# RJ45.net
KiCad netlist of a schematic drawn in Altium Designer
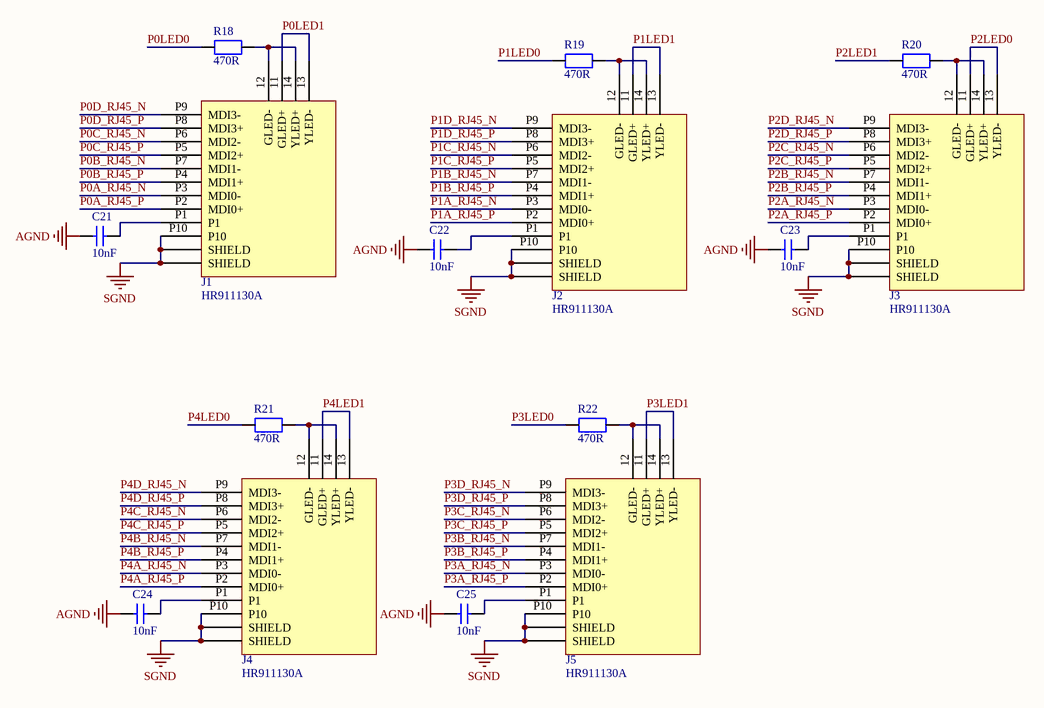
[diagram p0: RJ45.SchDoc]

(export (version "E")
  (design (tool "Eeschema 10.0.6"))
  (components
    (comp (ref "C21")
      (value "10nF")
      (footprint "C-0603")
      (description "C-0603")
      (libsource (lib "Switch_Schlib") (part "C-0603"))
    )
    (comp (ref "C22")
      (value "10nF")
      (footprint "C-0603")
      (description "C-0603")
      (libsource (lib "Switch_Schlib") (part "C-0603"))
    )
    (comp (ref "C23")
      (value "10nF")
      (footprint "C-0603")
      (description "C-0603")
      (libsource (lib "Switch_Schlib") (part "C-0603"))
    )
    (comp (ref "C24")
      (value "10nF")
      (footprint "C-0603")
      (description "C-0603")
      (libsource (lib "Switch_Schlib") (part "C-0603"))
    )
    (comp (ref "C25")
      (value "10nF")
      (footprint "C-0603")
      (description "C-0603")
      (libsource (lib "Switch_Schlib") (part "C-0603"))
    )
    (comp (ref "J1")
      (value "HR911130A")
      (footprint "RJ45")
      (libsource (lib "Switch_Schlib") (part "HR911130A"))
    )
    (comp (ref "J2")
      (value "HR911130A")
      (footprint "RJ45")
      (libsource (lib "Switch_Schlib") (part "HR911130A"))
    )
    (comp (ref "J3")
      (value "HR911130A")
      (footprint "RJ45")
      (libsource (lib "Switch_Schlib") (part "HR911130A"))
    )
    (comp (ref "J4")
      (value "HR911130A")
      (footprint "RJ45")
      (libsource (lib "Switch_Schlib") (part "HR911130A"))
    )
    (comp (ref "J5")
      (value "HR911130A")
      (footprint "RJ45")
      (libsource (lib "Switch_Schlib") (part "HR911130A"))
    )
    (comp (ref "R18")
      (value "470R")
      (footprint "RESMELF3515L")
      (description "CSR-0204")
      (libsource (lib "Switch_Schlib") (part "CSR-0204"))
    )
    (comp (ref "R19")
      (value "470R")
      (footprint "RESMELF3515L")
      (description "CSR-0204")
      (libsource (lib "Switch_Schlib") (part "CSR-0204"))
    )
    (comp (ref "R20")
      (value "470R")
      (footprint "RESMELF3515L")
      (description "CSR-0204")
      (libsource (lib "Switch_Schlib") (part "CSR-0204"))
    )
    (comp (ref "R21")
      (value "470R")
      (footprint "RESMELF3515L")
      (description "CSR-0204")
      (libsource (lib "Switch_Schlib") (part "CSR-0204"))
    )
    (comp (ref "R22")
      (value "470R")
      (footprint "RESMELF3515L")
      (description "CSR-0204")
      (libsource (lib "Switch_Schlib") (part "CSR-0204"))
    )
  )
  (nets
    (net (code "1") (name "/P0A_RJ45_N") (class "Default")
      (node (ref "J1") (pin "P3") (pinfunction "MDI0-_P3") (pintype "passive"))
    )
    (net (code "2") (name "/P0A_RJ45_P") (class "Default")
      (node (ref "J1") (pin "P2") (pinfunction "MDI0+_P2") (pintype "passive"))
    )
    (net (code "3") (name "/P0B_RJ45_N") (class "Default")
      (node (ref "J1") (pin "P7") (pinfunction "MDI1-_P7") (pintype "passive"))
    )
    (net (code "4") (name "/P0B_RJ45_P") (class "Default")
      (node (ref "J1") (pin "P4") (pinfunction "MDI1+_P4") (pintype "passive"))
    )
    (net (code "5") (name "/P0C_RJ45_N") (class "Default")
      (node (ref "J1") (pin "P6") (pinfunction "MDI2-_P6") (pintype "passive"))
    )
    (net (code "6") (name "/P0C_RJ45_P") (class "Default")
      (node (ref "J1") (pin "P5") (pinfunction "MDI2+_P5") (pintype "passive"))
    )
    (net (code "7") (name "/P0D_RJ45_N") (class "Default")
      (node (ref "J1") (pin "P9") (pinfunction "MDI3-_P9") (pintype "passive"))
    )
    (net (code "8") (name "/P0D_RJ45_P") (class "Default")
      (node (ref "J1") (pin "P8") (pinfunction "MDI3+_P8") (pintype "passive"))
    )
    (net (code "9") (name "/P0LED0") (class "Default") (node (ref "R18") (pin "1") (pintype "passive")))
    (net (code "10") (name "/P0LED1") (class "Default")
      (node (ref "J1") (pin "11") (pinfunction "GLED+_11") (pintype "passive"))
      (node (ref "J1") (pin "13") (pinfunction "YLED-_13") (pintype "passive"))
    )
    (net (code "11") (name "/P1A_RJ45_N") (class "Default")
      (node (ref "J2") (pin "P3") (pinfunction "MDI0-_P3") (pintype "passive"))
    )
    (net (code "12") (name "/P1A_RJ45_P") (class "Default")
      (node (ref "J2") (pin "P2") (pinfunction "MDI0+_P2") (pintype "passive"))
    )
    (net (code "13") (name "/P1B_RJ45_N") (class "Default")
      (node (ref "J2") (pin "P7") (pinfunction "MDI1-_P7") (pintype "passive"))
    )
    (net (code "14") (name "/P1B_RJ45_P") (class "Default")
      (node (ref "J2") (pin "P4") (pinfunction "MDI1+_P4") (pintype "passive"))
    )
    (net (code "15") (name "/P1C_RJ45_N") (class "Default")
      (node (ref "J2") (pin "P6") (pinfunction "MDI2-_P6") (pintype "passive"))
    )
    (net (code "16") (name "/P1C_RJ45_P") (class "Default")
      (node (ref "J2") (pin "P5") (pinfunction "MDI2+_P5") (pintype "passive"))
    )
    (net (code "17") (name "/P1D_RJ45_N") (class "Default")
      (node (ref "J2") (pin "P9") (pinfunction "MDI3-_P9") (pintype "passive"))
    )
    (net (code "18") (name "/P1D_RJ45_P") (class "Default")
      (node (ref "J2") (pin "P8") (pinfunction "MDI3+_P8") (pintype "passive"))
    )
    (net (code "19") (name "/P1LED0") (class "Default") (node (ref "R19") (pin "1") (pintype "passive")))
    (net (code "20") (name "/P1LED1") (class "Default")
      (node (ref "J2") (pin "11") (pinfunction "GLED+_11") (pintype "passive"))
      (node (ref "J2") (pin "13") (pinfunction "YLED-_13") (pintype "passive"))
    )
    (net (code "21") (name "/P2A_RJ45_N") (class "Default")
      (node (ref "J3") (pin "P3") (pinfunction "MDI0-_P3") (pintype "passive"))
    )
    (net (code "22") (name "/P2A_RJ45_P") (class "Default")
      (node (ref "J3") (pin "P2") (pinfunction "MDI0+_P2") (pintype "passive"))
    )
    (net (code "23") (name "/P2B_RJ45_N") (class "Default")
      (node (ref "J3") (pin "P7") (pinfunction "MDI1-_P7") (pintype "passive"))
    )
    (net (code "24") (name "/P2B_RJ45_P") (class "Default")
      (node (ref "J3") (pin "P4") (pinfunction "MDI1+_P4") (pintype "passive"))
    )
    (net (code "25") (name "/P2C_RJ45_N") (class "Default")
      (node (ref "J3") (pin "P6") (pinfunction "MDI2-_P6") (pintype "passive"))
    )
    (net (code "26") (name "/P2C_RJ45_P") (class "Default")
      (node (ref "J3") (pin "P5") (pinfunction "MDI2+_P5") (pintype "passive"))
    )
    (net (code "27") (name "/P2D_RJ45_N") (class "Default")
      (node (ref "J3") (pin "P9") (pinfunction "MDI3-_P9") (pintype "passive"))
    )
    (net (code "28") (name "/P2D_RJ45_P") (class "Default")
      (node (ref "J3") (pin "P8") (pinfunction "MDI3+_P8") (pintype "passive"))
    )
    (net (code "29") (name "/P2LED0") (class "Default")
      (node (ref "J3") (pin "11") (pinfunction "GLED+_11") (pintype "passive"))
      (node (ref "J3") (pin "13") (pinfunction "YLED-_13") (pintype "passive"))
    )
    (net (code "30") (name "/P2LED1") (class "Default") (node (ref "R20") (pin "1") (pintype "passive")))
    (net (code "31") (name "/P3A_RJ45_N") (class "Default")
      (node (ref "J5") (pin "P3") (pinfunction "MDI0-_P3") (pintype "passive"))
    )
    (net (code "32") (name "/P3A_RJ45_P") (class "Default")
      (node (ref "J5") (pin "P2") (pinfunction "MDI0+_P2") (pintype "passive"))
    )
    (net (code "33") (name "/P3B_RJ45_N") (class "Default")
      (node (ref "J5") (pin "P7") (pinfunction "MDI1-_P7") (pintype "passive"))
    )
    (net (code "34") (name "/P3B_RJ45_P") (class "Default")
      (node (ref "J5") (pin "P4") (pinfunction "MDI1+_P4") (pintype "passive"))
    )
    (net (code "35") (name "/P3C_RJ45_N") (class "Default")
      (node (ref "J5") (pin "P6") (pinfunction "MDI2-_P6") (pintype "passive"))
    )
    (net (code "36") (name "/P3C_RJ45_P") (class "Default")
      (node (ref "J5") (pin "P5") (pinfunction "MDI2+_P5") (pintype "passive"))
    )
    (net (code "37") (name "/P3D_RJ45_N") (class "Default")
      (node (ref "J5") (pin "P9") (pinfunction "MDI3-_P9") (pintype "passive"))
    )
    (net (code "38") (name "/P3D_RJ45_P") (class "Default")
      (node (ref "J5") (pin "P8") (pinfunction "MDI3+_P8") (pintype "passive"))
    )
    (net (code "39") (name "/P3LED0") (class "Default") (node (ref "R22") (pin "1") (pintype "passive")))
    (net (code "40") (name "/P3LED1") (class "Default")
      (node (ref "J5") (pin "11") (pinfunction "GLED+_11") (pintype "passive"))
      (node (ref "J5") (pin "13") (pinfunction "YLED-_13") (pintype "passive"))
    )
    (net (code "41") (name "/P4A_RJ45_N") (class "Default")
      (node (ref "J4") (pin "P3") (pinfunction "MDI0-_P3") (pintype "passive"))
    )
    (net (code "42") (name "/P4A_RJ45_P") (class "Default")
      (node (ref "J4") (pin "P2") (pinfunction "MDI0+_P2") (pintype "passive"))
    )
    (net (code "43") (name "/P4B_RJ45_N") (class "Default")
      (node (ref "J4") (pin "P7") (pinfunction "MDI1-_P7") (pintype "passive"))
    )
    (net (code "44") (name "/P4B_RJ45_P") (class "Default")
      (node (ref "J4") (pin "P4") (pinfunction "MDI1+_P4") (pintype "passive"))
    )
    (net (code "45") (name "/P4C_RJ45_N") (class "Default")
      (node (ref "J4") (pin "P6") (pinfunction "MDI2-_P6") (pintype "passive"))
    )
    (net (code "46") (name "/P4C_RJ45_P") (class "Default")
      (node (ref "J4") (pin "P5") (pinfunction "MDI2+_P5") (pintype "passive"))
    )
    (net (code "47") (name "/P4D_RJ45_N") (class "Default")
      (node (ref "J4") (pin "P9") (pinfunction "MDI3-_P9") (pintype "passive"))
    )
    (net (code "48") (name "/P4D_RJ45_P") (class "Default")
      (node (ref "J4") (pin "P8") (pinfunction "MDI3+_P8") (pintype "passive"))
    )
    (net (code "49") (name "/P4LED0") (class "Default") (node (ref "R21") (pin "1") (pintype "passive")))
    (net (code "50") (name "/P4LED1") (class "Default")
      (node (ref "J4") (pin "11") (pinfunction "GLED+_11") (pintype "passive"))
      (node (ref "J4") (pin "13") (pinfunction "YLED-_13") (pintype "passive"))
    )
    (net (code "51") (name "AGND") (class "Default")
      (node (ref "C21") (pin "2") (pintype "passive"))
      (node (ref "C22") (pin "2") (pintype "passive"))
      (node (ref "C23") (pin "2") (pintype "passive"))
      (node (ref "C24") (pin "1") (pintype "passive"))
      (node (ref "C25") (pin "2") (pintype "passive"))
    )
    (net (code "52") (name "Net-(C21-Pad1)") (class "Default")
      (node (ref "C21") (pin "1") (pintype "passive"))
      (node (ref "J1") (pin "P1") (pinfunction "P1_P1") (pintype "passive"))
    )
    (net (code "53") (name "Net-(C22-Pad1)") (class "Default")
      (node (ref "C22") (pin "1") (pintype "passive"))
      (node (ref "J2") (pin "P1") (pinfunction "P1_P1") (pintype "passive"))
    )
    (net (code "54") (name "Net-(C23-Pad1)") (class "Default")
      (node (ref "C23") (pin "1") (pintype "passive"))
      (node (ref "J3") (pin "P1") (pinfunction "P1_P1") (pintype "passive"))
    )
    (net (code "55") (name "Net-(C24-Pad2)") (class "Default")
      (node (ref "C24") (pin "2") (pintype "passive"))
      (node (ref "J4") (pin "P1") (pinfunction "P1_P1") (pintype "passive"))
    )
    (net (code "56") (name "Net-(C25-Pad1)") (class "Default")
      (node (ref "C25") (pin "1") (pintype "passive"))
      (node (ref "J5") (pin "P1") (pinfunction "P1_P1") (pintype "passive"))
    )
    (net (code "57") (name "Net-(J1-GLED-)") (class "Default")
      (node (ref "J1") (pin "12") (pinfunction "GLED-_12") (pintype "passive"))
      (node (ref "J1") (pin "14") (pinfunction "YLED+_14") (pintype "passive"))
      (node (ref "R18") (pin "2") (pintype "passive"))
    )
    (net (code "58") (name "Net-(J2-GLED-)") (class "Default")
      (node (ref "J2") (pin "12") (pinfunction "GLED-_12") (pintype "passive"))
      (node (ref "J2") (pin "14") (pinfunction "YLED+_14") (pintype "passive"))
      (node (ref "R19") (pin "2") (pintype "passive"))
    )
    (net (code "59") (name "Net-(J3-GLED-)") (class "Default")
      (node (ref "J3") (pin "12") (pinfunction "GLED-_12") (pintype "passive"))
      (node (ref "J3") (pin "14") (pinfunction "YLED+_14") (pintype "passive"))
      (node (ref "R20") (pin "2") (pintype "passive"))
    )
    (net (code "60") (name "Net-(J4-GLED-)") (class "Default")
      (node (ref "J4") (pin "12") (pinfunction "GLED-_12") (pintype "passive"))
      (node (ref "J4") (pin "14") (pinfunction "YLED+_14") (pintype "passive"))
      (node (ref "R21") (pin "2") (pintype "passive"))
    )
    (net (code "61") (name "Net-(J5-GLED-)") (class "Default")
      (node (ref "J5") (pin "12") (pinfunction "GLED-_12") (pintype "passive"))
      (node (ref "J5") (pin "14") (pinfunction "YLED+_14") (pintype "passive"))
      (node (ref "R22") (pin "2") (pintype "passive"))
    )
    (net (code "62") (name "SGND") (class "Default")
      (node (ref "J1") (pin "P10") (pinfunction "P10_P10") (pintype "passive"))
      (node (ref "J1") (pin "SHIELD0") (pinfunction "SHIELD_SHIELD0") (pintype "passive"))
      (node (ref "J1") (pin "SHIELD1") (pinfunction "SHIELD_SHIELD1") (pintype "passive"))
      (node (ref "J2") (pin "P10") (pinfunction "P10_P10") (pintype "passive"))
      (node (ref "J2") (pin "SHIELD0") (pinfunction "SHIELD_SHIELD0") (pintype "passive"))
      (node (ref "J2") (pin "SHIELD1") (pinfunction "SHIELD_SHIELD1") (pintype "passive"))
      (node (ref "J3") (pin "P10") (pinfunction "P10_P10") (pintype "passive"))
      (node (ref "J3") (pin "SHIELD0") (pinfunction "SHIELD_SHIELD0") (pintype "passive"))
      (node (ref "J3") (pin "SHIELD1") (pinfunction "SHIELD_SHIELD1") (pintype "passive"))
      (node (ref "J4") (pin "P10") (pinfunction "P10_P10") (pintype "passive"))
      (node (ref "J4") (pin "SHIELD0") (pinfunction "SHIELD_SHIELD0") (pintype "passive"))
      (node (ref "J4") (pin "SHIELD1") (pinfunction "SHIELD_SHIELD1") (pintype "passive"))
      (node (ref "J5") (pin "P10") (pinfunction "P10_P10") (pintype "passive"))
      (node (ref "J5") (pin "SHIELD0") (pinfunction "SHIELD_SHIELD0") (pintype "passive"))
      (node (ref "J5") (pin "SHIELD1") (pinfunction "SHIELD_SHIELD1") (pintype "passive"))
    )
  )
)
